# openSX70_PATHFINDER_V5_6-SEEED_20180611.net
KiCad netlist of a schematic drawn in EAGLE
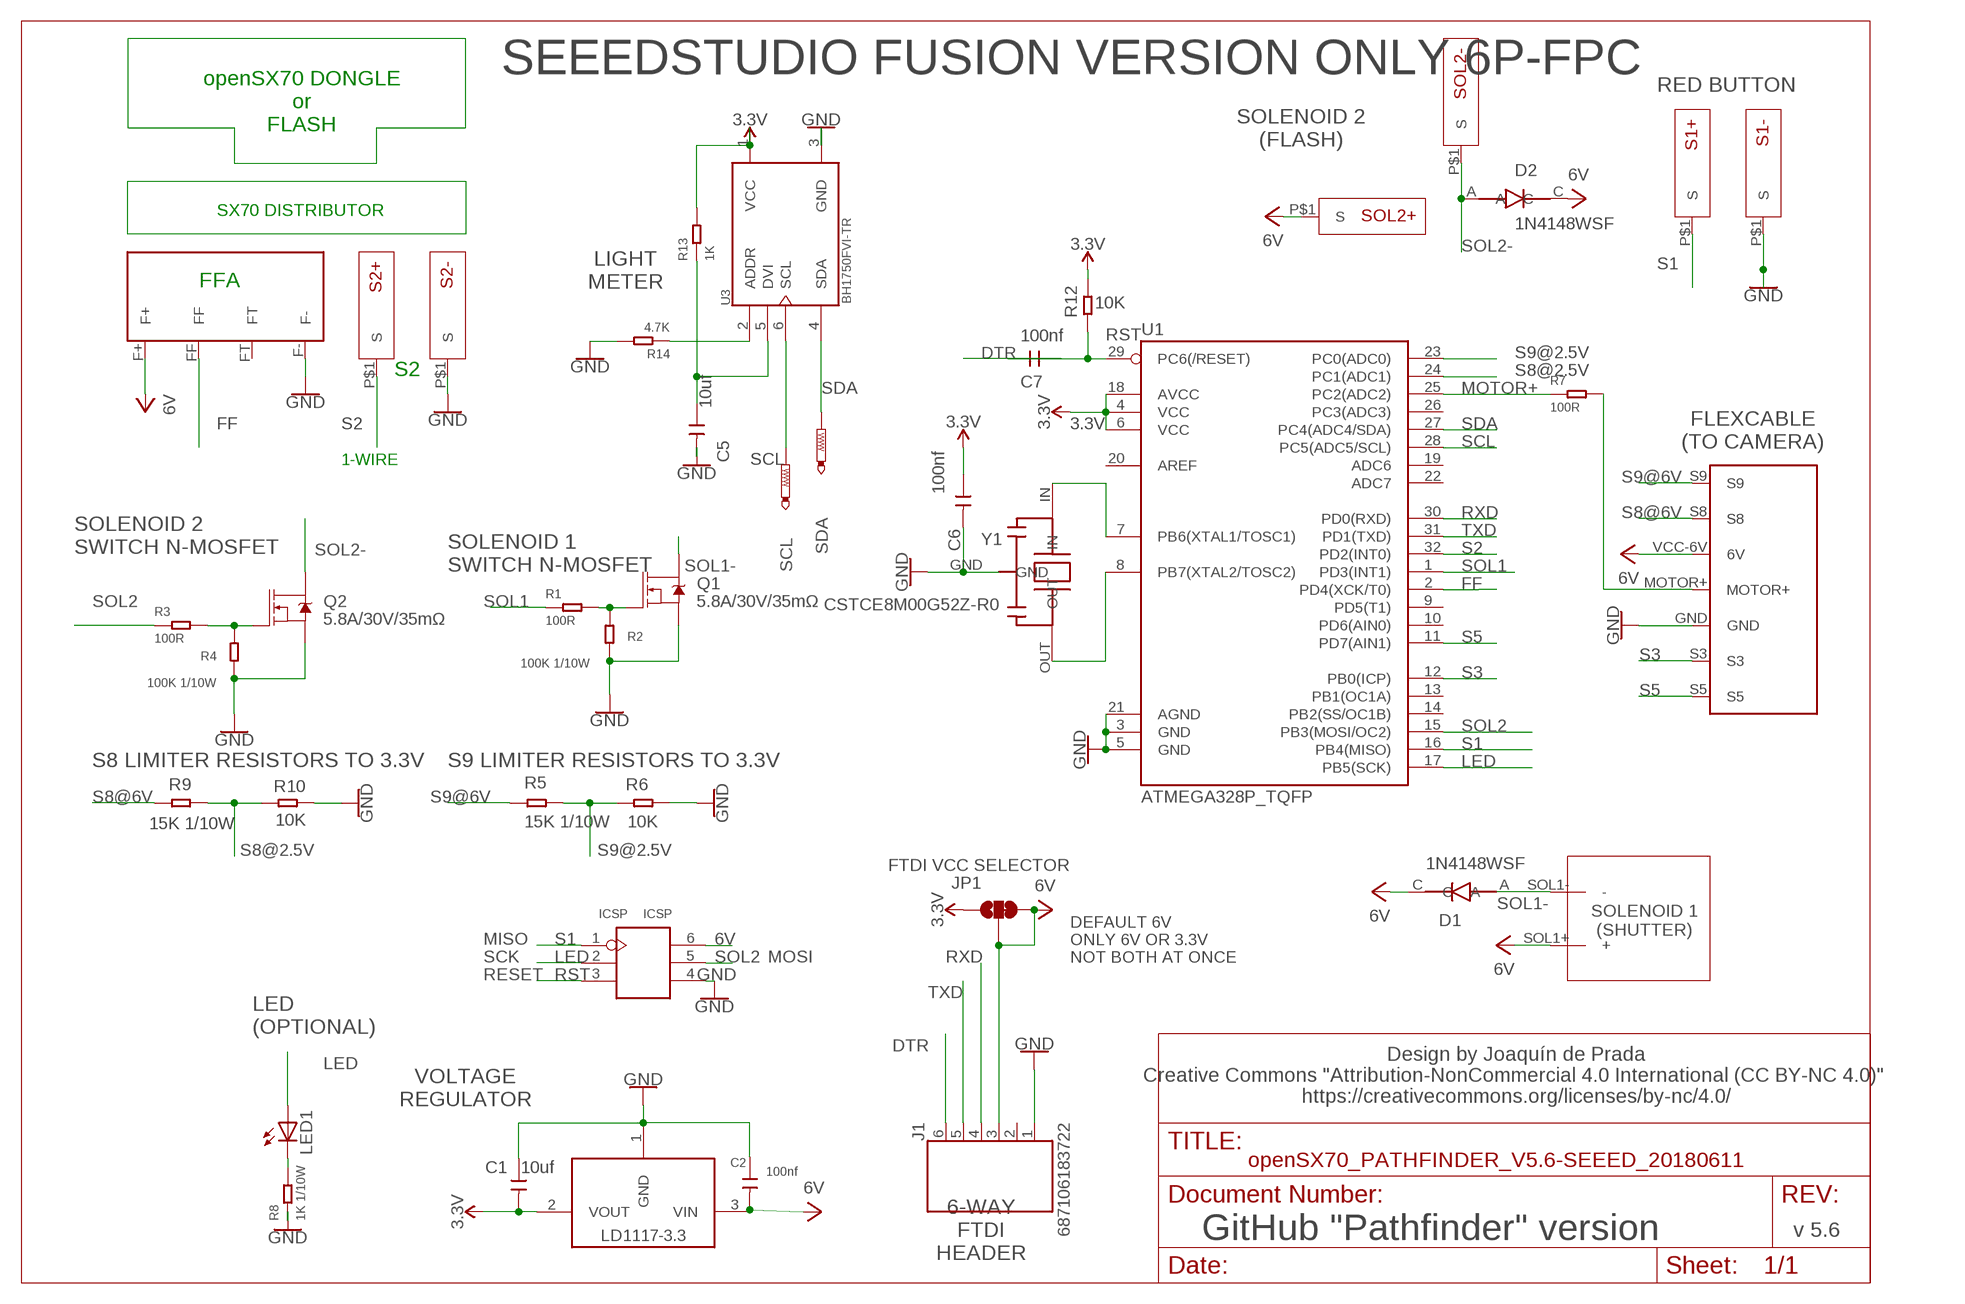
[diagram p0: schematic, sheet 1]

(export (version "E")
  (design (tool "Eeschema 10.0.6"))
  (components
    (comp (ref "C1")
      (value "10uf")
      (footprint "eagle-import:C0603")
      (fields (field (name "MPN") "CC0603KRX5R6BB106"))
      (libsource (lib "eagle-import") (part "CERAMIC-10UF-10V-10%-X5R(0603)"))
    )
    (comp (ref "C2")
      (value "100nf")
      (footprint "eagle-import:C0603")
      (fields (field (name "MPN") "CC0603KRX7R9BB104"))
      (libsource (lib "eagle-import") (part "CERAMIC-100NF-50V-10%-X7R(0603)"))
    )
    (comp (ref "C5")
      (value "10uf")
      (footprint "eagle-import:C0603")
      (fields (field (name "MPN") "CC0603KRX5R6BB106"))
      (libsource (lib "eagle-import") (part "CERAMIC-10UF-10V-10%-X5R(0603)"))
    )
    (comp (ref "C6")
      (value "100nf")
      (footprint "eagle-import:C0603")
      (fields (field (name "MPN") "CC0603KRX7R9BB104"))
      (libsource (lib "eagle-import") (part "CERAMIC-100NF-50V-10%-X7R(0603)"))
    )
    (comp (ref "C7")
      (value "100nf")
      (footprint "eagle-import:C0603")
      (fields (field (name "MPN") "CC0603KRX7R9BB104"))
      (libsource (lib "eagle-import") (part "CERAMIC-100NF-50V-10%-X7R(0603)"))
    )
    (comp (ref "D1")
      (value "1N4148WSF")
      (footprint "eagle-import:SODFL2512X100N")
      (fields (field (name "MANUFACTURER") "Fairchild Semiconductor"))
      (libsource (lib "eagle-import") (part "1N4148WS"))
    )
    (comp (ref "D2")
      (value "1N4148WSF")
      (footprint "eagle-import:SODFL2512X100N")
      (fields (field (name "MANUFACTURER") "Fairchild Semiconductor"))
      (libsource (lib "eagle-import") (part "1N4148WS"))
    )
    (comp (ref "ICSP")
      (value "ICSP")
      (footprint "eagle-import:H2X3-2.54")
      (libsource (lib "eagle-import") (part "ICSP"))
    )
    (comp (ref "J1")
      (value "687106183722")
      (footprint "eagle-import:687106183722")
      (fields (field (name "MF") "Wurth Electronics"))
      (libsource (lib "eagle-import") (part "687106183722"))
    )
    (comp (ref "JP1")
      (value "FTDI VCC SELECTOR")
      (footprint "eagle-import:SMT-JUMPER_3_1-NC_TRACE_SILK")
      (libsource (lib "eagle-import") (part "JUMPER-SMT_3_1-NC_TRACE_SILK"))
    )
    (comp (ref "LD11172.5V")
      (value "LD1117 2.5V")
      (footprint "eagle-import:SOT223")
      (fields (field (name "MF") "Advanced Monolithic Systems") (field (name "MP") "AMS1117-5.0"))
      (libsource (lib "eagle-import") (part "LD1117-3.3"))
    )
    (comp (ref "LED1")
      (value "LEDCHIPLED_0805")
      (footprint "eagle-import:CHIPLED_0805")
      (libsource (lib "eagle-import") (part "LEDCHIPLED_0805"))
    )
    (comp (ref "Q1")
      (value "5.8A/30V/35mΩ")
      (footprint "eagle-import:SOT23-3")
      (libsource (lib "eagle-import") (part "MOSFET-NCH-AO3404A"))
    )
    (comp (ref "Q2")
      (value "5.8A/30V/35mΩ")
      (footprint "eagle-import:SOT23-3")
      (libsource (lib "eagle-import") (part "MOSFET-NCH-AO3404A"))
    )
    (comp (ref "R1")
      (value "100R")
      (footprint "eagle-import:R0603")
      (fields (field (name "MPN") "RC0603JR-07100RL"))
      (libsource (lib "eagle-import") (part "SMD-RES-100R-5%-1/10W(0603)"))
    )
    (comp (ref "R2")
      (value "100K 1/10W")
      (footprint "eagle-import:R0603")
      (fields (field (name "MPN") "RC0603JR-07100KL"))
      (libsource (lib "eagle-import") (part "SMD-RES-100K-5%-1/10W(0603)"))
    )
    (comp (ref "R3")
      (value "100R")
      (footprint "eagle-import:R0603")
      (fields (field (name "MPN") "RC0603JR-07100RL"))
      (libsource (lib "eagle-import") (part "SMD-RES-100R-5%-1/10W(0603)"))
    )
    (comp (ref "R4")
      (value "100K 1/10W")
      (footprint "eagle-import:R0603")
      (fields (field (name "MPN") "RC0603JR-07100KL"))
      (libsource (lib "eagle-import") (part "SMD-RES-100K-5%-1/10W(0603)"))
    )
    (comp (ref "R5")
      (value "15K 1/10W")
      (footprint "eagle-import:R0603")
      (fields (field (name "MPN") "RC0603FR-0715KL"))
      (libsource (lib "eagle-import") (part "SMD-RES-15K-1%-1/10W(0603)"))
    )
    (comp (ref "R6")
      (value "10K")
      (footprint "eagle-import:R0603")
      (fields (field (name "MPN") "RC0603FR-0710KL"))
      (libsource (lib "eagle-import") (part "SMD-RES-10K-1%-1/10W(0603)"))
    )
    (comp (ref "R7")
      (value "100R")
      (footprint "eagle-import:R0603")
      (fields (field (name "MPN") "RC0603JR-07100RL"))
      (libsource (lib "eagle-import") (part "SMD-RES-100R-5%-1/10W(0603)"))
    )
    (comp (ref "R8")
      (value "1K 1/10W")
      (footprint "eagle-import:R0603")
      (fields (field (name "MPN") "RC0603JR-071KL"))
      (libsource (lib "eagle-import") (part "SMD-RES-1K-5%-1/10W(0603)"))
    )
    (comp (ref "R9")
      (value "15K 1/10W")
      (footprint "eagle-import:R0603")
      (fields (field (name "MPN") "RC0603FR-0715KL"))
      (libsource (lib "eagle-import") (part "SMD-RES-15K-1%-1/10W(0603)"))
    )
    (comp (ref "R10")
      (value "10K")
      (footprint "eagle-import:R0603")
      (fields (field (name "MPN") "RC0603FR-0710KL"))
      (libsource (lib "eagle-import") (part "SMD-RES-10K-1%-1/10W(0603)"))
    )
    (comp (ref "R12")
      (value "10K")
      (footprint "eagle-import:R0603")
      (fields (field (name "MPN") "RC0603FR-0710KL"))
      (libsource (lib "eagle-import") (part "SMD-RES-10K-1%-1/10W(0603)"))
    )
    (comp (ref "R13")
      (value "1K")
      (footprint "eagle-import:R0603")
      (fields (field (name "MPN") "RC0603FR-071KL"))
      (libsource (lib "eagle-import") (part "SMD-RES-1K-1%-1/10W(0603)"))
    )
    (comp (ref "R14")
      (value "4.7K")
      (footprint "eagle-import:R0603")
      (fields (field (name "MPN") "RC0603JR-074K7L"))
      (libsource (lib "eagle-import") (part "SMD-RES-4.7K-5%-1/10W(0603)"))
    )
    (comp (ref "S1+")
      (value "SX70-S-PAD-NEW")
      (footprint "eagle-import:SX70-S-PAD2")
      (libsource (lib "eagle-import") (part "SX70-S-PAD-NEW"))
    )
    (comp (ref "S1-")
      (value "SX70-S-PAD-NEW")
      (footprint "eagle-import:SX70-S-PAD2")
      (libsource (lib "eagle-import") (part "SX70-S-PAD-NEW"))
    )
    (comp (ref "S2+")
      (value "SX70-S-PAD-NEW")
      (footprint "eagle-import:SX70-S-PAD2")
      (libsource (lib "eagle-import") (part "SX70-S-PAD-NEW"))
    )
    (comp (ref "S2-")
      (value "SX70-S-PAD-NEW")
      (footprint "eagle-import:SX70-S-PAD2")
      (libsource (lib "eagle-import") (part "SX70-S-PAD-NEW"))
    )
    (comp (ref "SCL")
      (value "PTR1TP08R")
      (footprint "eagle-import:TP08R")
      (libsource (lib "eagle-import") (part "PTR1TP08R"))
    )
    (comp (ref "SDA")
      (value "PTR1TP08R")
      (footprint "eagle-import:TP08R")
      (libsource (lib "eagle-import") (part "PTR1TP08R"))
    )
    (comp (ref "SOL1")
      (value "SX70-SOLENOID1-2PADS")
      (footprint "eagle-import:SX70-SOLENOID1-2")
      (libsource (lib "eagle-import") (part "SX70-SOLENOID1-2PADS"))
    )
    (comp (ref "SOL2+")
      (value "SX70-S-PAD-NEW")
      (footprint "eagle-import:SX70-S-PAD2")
      (libsource (lib "eagle-import") (part "SX70-S-PAD-NEW"))
    )
    (comp (ref "SOL2-")
      (value "SX70-S-PAD-NEW")
      (footprint "eagle-import:SX70-S-PAD2")
      (libsource (lib "eagle-import") (part "SX70-S-PAD-NEW"))
    )
    (comp (ref "U$1")
      (value "SX70-7-PAD")
      (footprint "eagle-import:SX70-7-PAD")
      (libsource (lib "eagle-import") (part "SX70-7-PAD"))
    )
    (comp (ref "U$2")
      (value "FFA")
      (footprint "eagle-import:FFA-PAD-PACKAGE")
      (libsource (lib "eagle-import") (part "SX70-FFA-PAD"))
    )
    (comp (ref "U1")
      (value "ATMEGA328P_TQFP")
      (footprint "eagle-import:TQFP32-08")
      (libsource (lib "eagle-import") (part "ATMEGA328P_TQFP"))
    )
    (comp (ref "U3")
      (value "BH1750FVI-TR")
      (footprint "eagle-import:SOTFL50P300X75-6N")
      (fields (field (name "MF") "Rohm"))
      (libsource (lib "eagle-import") (part "BH1750FVI-TR"))
    )
    (comp (ref "Y1")
      (value "CSTCE8M00G52Z-R0")
      (footprint "eagle-import:CFP95P160X100-3N")
      (fields (field (name "MF") "Murata") (field (name "MP") "CSTCE16M0V53-R0"))
      (libsource (lib "eagle-import") (part "CSTCE16M0V53-R0"))
    )
  )
  (nets
    (net (code "1") (name "/DTR") (class "Default")
      (node (ref "C7") (pin "1") (pinfunction "1_1") (pintype "passive"))
      (node (ref "J1") (pin "6") (pinfunction "1_6") (pintype "passive"))
    )
    (net (code "2") (name "/FF") (class "Default")
      (node (ref "U$2") (pin "FF") (pinfunction "FF_FF") (pintype "bidirectional"))
      (node (ref "U1") (pin "2") (pinfunction "PD4(XCK/T0)_2") (pintype "bidirectional"))
    )
    (net (code "3") (name "/LED") (class "Default")
      (node (ref "ICSP") (pin "2") (pinfunction "SCK_2") (pintype "bidirectional"))
      (node (ref "LED1") (pin "A") (pinfunction "A_A") (pintype "passive"))
      (node (ref "U1") (pin "17") (pinfunction "PB5(SCK)_17") (pintype "bidirectional"))
    )
    (net (code "4") (name "/MOTOR+") (class "Default")
      (node (ref "R7") (pin "1") (pinfunction "1_1") (pintype "passive"))
      (node (ref "U1") (pin "25") (pinfunction "PC2(ADC2)_25") (pintype "bidirectional"))
    )
    (net (code "5") (name "/RST") (class "Default")
      (node (ref "C7") (pin "2") (pinfunction "2_2") (pintype "passive"))
      (node (ref "ICSP") (pin "3") (pinfunction "RST_3") (pintype "bidirectional"))
      (node (ref "R12") (pin "1") (pinfunction "1_1") (pintype "passive"))
      (node (ref "U1") (pin "29") (pinfunction "PC6(/RESET)_29") (pintype "bidirectional"))
    )
    (net (code "6") (name "/RXD") (class "Default")
      (node (ref "J1") (pin "4") (pinfunction "3_4") (pintype "passive"))
      (node (ref "U1") (pin "30") (pinfunction "PD0(RXD)_30") (pintype "bidirectional"))
    )
    (net (code "7") (name "/S1") (class "Default")
      (node (ref "ICSP") (pin "1") (pinfunction "MISO_1") (pintype "bidirectional"))
      (node (ref "S1+") (pin "P$1") (pinfunction "S_P$1") (pintype "bidirectional"))
      (node (ref "U1") (pin "16") (pinfunction "PB4(MISO)_16") (pintype "bidirectional"))
    )
    (net (code "8") (name "/S2") (class "Default")
      (node (ref "S2+") (pin "P$1") (pinfunction "S_P$1") (pintype "bidirectional"))
      (node (ref "U1") (pin "32") (pinfunction "PD2(INT0)_32") (pintype "bidirectional"))
    )
    (net (code "9") (name "/S3") (class "Default")
      (node (ref "U$1") (pin "S3") (pinfunction "S3_S3") (pintype "bidirectional"))
      (node (ref "U1") (pin "12") (pinfunction "PB0(ICP)_12") (pintype "bidirectional"))
    )
    (net (code "10") (name "/S5") (class "Default")
      (node (ref "U$1") (pin "S5") (pinfunction "S5_S5") (pintype "bidirectional"))
      (node (ref "U1") (pin "11") (pinfunction "PD7(AIN1)_11") (pintype "bidirectional"))
    )
    (net (code "11") (name "/S8@2.5V") (class "Default")
      (node (ref "R10") (pin "1") (pinfunction "1_1") (pintype "passive"))
      (node (ref "R9") (pin "2") (pinfunction "2_2") (pintype "passive"))
      (node (ref "U1") (pin "24") (pinfunction "PC1(ADC1)_24") (pintype "bidirectional"))
    )
    (net (code "12") (name "/S8@6V") (class "Default")
      (node (ref "R9") (pin "1") (pinfunction "1_1") (pintype "passive"))
      (node (ref "U$1") (pin "S8") (pinfunction "S8_S8") (pintype "bidirectional"))
    )
    (net (code "13") (name "/S9@2.5V") (class "Default")
      (node (ref "R5") (pin "2") (pinfunction "2_2") (pintype "passive"))
      (node (ref "R6") (pin "1") (pinfunction "1_1") (pintype "passive"))
      (node (ref "U1") (pin "23") (pinfunction "PC0(ADC0)_23") (pintype "bidirectional"))
    )
    (net (code "14") (name "/S9@6V") (class "Default")
      (node (ref "R5") (pin "1") (pinfunction "1_1") (pintype "passive"))
      (node (ref "U$1") (pin "S9") (pinfunction "S9_S9") (pintype "bidirectional"))
    )
    (net (code "15") (name "/SCL") (class "Default")
      (node (ref "SCL") (pin "TP") (pinfunction "TP_TP") (pintype "input"))
      (node (ref "U1") (pin "28") (pinfunction "PC5(ADC5/SCL)_28") (pintype "bidirectional"))
      (node (ref "U3") (pin "6") (pinfunction "SCL_6") (pintype "input"))
    )
    (net (code "16") (name "/SDA") (class "Default")
      (node (ref "SDA") (pin "TP") (pinfunction "TP_TP") (pintype "input"))
      (node (ref "U1") (pin "27") (pinfunction "PC4(ADC4/SDA)_27") (pintype "bidirectional"))
      (node (ref "U3") (pin "4") (pinfunction "SDA_4") (pintype "bidirectional"))
    )
    (net (code "17") (name "/SOL1") (class "Default")
      (node (ref "R1") (pin "1") (pinfunction "1_1") (pintype "passive"))
      (node (ref "U1") (pin "1") (pinfunction "PD3(INT1)_1") (pintype "bidirectional"))
    )
    (net (code "18") (name "/SOL1-") (class "Default")
      (node (ref "D1") (pin "A") (pinfunction "A_A") (pintype "passive"))
      (node (ref "Q1") (pin "3") (pinfunction "D_3") (pintype "bidirectional"))
      (node (ref "SOL1") (pin "SOL1-") (pinfunction "-_SOL1-") (pintype "bidirectional"))
    )
    (net (code "19") (name "/SOL2") (class "Default")
      (node (ref "ICSP") (pin "5") (pinfunction "MOSI_5") (pintype "bidirectional"))
      (node (ref "R3") (pin "1") (pinfunction "1_1") (pintype "passive"))
      (node (ref "U1") (pin "15") (pinfunction "PB3(MOSI/OC2)_15") (pintype "bidirectional"))
    )
    (net (code "20") (name "/SOL2-") (class "Default")
      (node (ref "D2") (pin "A") (pinfunction "A_A") (pintype "passive"))
      (node (ref "Q2") (pin "3") (pinfunction "D_3") (pintype "bidirectional"))
      (node (ref "SOL2-") (pin "P$1") (pinfunction "S_P$1") (pintype "bidirectional"))
    )
    (net (code "21") (name "/TXD") (class "Default")
      (node (ref "J1") (pin "5") (pinfunction "2_5") (pintype "passive"))
      (node (ref "U1") (pin "31") (pinfunction "PD1(TXD)_31") (pintype "bidirectional"))
    )
    (net (code "22") (name "3.3V") (class "Default")
      (node (ref "C1") (pin "2") (pinfunction "2_2") (pintype "passive"))
      (node (ref "C6") (pin "1") (pinfunction "1_1") (pintype "passive"))
      (node (ref "JP1") (pin "1") (pinfunction "1_1") (pintype "passive"))
      (node (ref "LD11172.5V") (pin "2") (pinfunction "VOUT_2") (pintype "bidirectional"))
      (node (ref "R12") (pin "2") (pinfunction "2_2") (pintype "passive"))
      (node (ref "R13") (pin "2") (pinfunction "2_2") (pintype "passive"))
      (node (ref "U1") (pin "18") (pinfunction "AVCC_18") (pintype "bidirectional"))
      (node (ref "U1") (pin "4") (pinfunction "VCC_4") (pintype "bidirectional"))
      (node (ref "U1") (pin "6") (pinfunction "VCC_6") (pintype "bidirectional"))
      (node (ref "U3") (pin "1") (pinfunction "VCC_1") (pintype "power_in"))
    )
    (net (code "23") (name "6V") (class "Default")
      (node (ref "C2") (pin "2") (pinfunction "2_2") (pintype "passive"))
      (node (ref "D1") (pin "C") (pinfunction "C_C") (pintype "passive"))
      (node (ref "D2") (pin "C") (pinfunction "C_C") (pintype "passive"))
      (node (ref "ICSP") (pin "6") (pinfunction "VCC_6") (pintype "bidirectional"))
      (node (ref "J1") (pin "3") (pinfunction "4_3") (pintype "passive"))
      (node (ref "JP1") (pin "2") (pinfunction "2_2") (pintype "passive"))
      (node (ref "JP1") (pin "3") (pinfunction "3_3") (pintype "passive"))
      (node (ref "LD11172.5V") (pin "3") (pinfunction "VIN_3") (pintype "bidirectional"))
      (node (ref "SOL1") (pin "SOL1+") (pinfunction "+_SOL1+") (pintype "bidirectional"))
      (node (ref "SOL2+") (pin "P$1") (pinfunction "S_P$1") (pintype "bidirectional"))
      (node (ref "U$1") (pin "VCC-6V") (pinfunction "6V_VCC-6V") (pintype "bidirectional"))
      (node (ref "U$2") (pin "F+") (pinfunction "F+_F+") (pintype "bidirectional"))
    )
    (net (code "24") (name "GND") (class "Default")
      (node (ref "C1") (pin "1") (pinfunction "1_1") (pintype "passive"))
      (node (ref "C2") (pin "1") (pinfunction "1_1") (pintype "passive"))
      (node (ref "C5") (pin "2") (pinfunction "2_2") (pintype "passive"))
      (node (ref "C6") (pin "2") (pinfunction "2_2") (pintype "passive"))
      (node (ref "ICSP") (pin "4") (pinfunction "GND_4") (pintype "bidirectional"))
      (node (ref "J1") (pin "1") (pinfunction "6_1") (pintype "passive"))
      (node (ref "LD11172.5V") (pin "1") (pinfunction "GND_1") (pintype "bidirectional"))
      (node (ref "Q1") (pin "2") (pinfunction "S_2") (pintype "bidirectional"))
      (node (ref "Q2") (pin "2") (pinfunction "S_2") (pintype "bidirectional"))
      (node (ref "R10") (pin "2") (pinfunction "2_2") (pintype "passive"))
      (node (ref "R14") (pin "2") (pinfunction "2_2") (pintype "passive"))
      (node (ref "R2") (pin "1") (pinfunction "1_1") (pintype "passive"))
      (node (ref "R4") (pin "1") (pinfunction "1_1") (pintype "passive"))
      (node (ref "R6") (pin "2") (pinfunction "2_2") (pintype "passive"))
      (node (ref "R8") (pin "1") (pinfunction "1_1") (pintype "passive"))
      (node (ref "S1-") (pin "P$1") (pinfunction "S_P$1") (pintype "bidirectional"))
      (node (ref "S2-") (pin "P$1") (pinfunction "S_P$1") (pintype "bidirectional"))
      (node (ref "U$1") (pin "GND") (pinfunction "GND_GND") (pintype "bidirectional"))
      (node (ref "U$2") (pin "F-") (pinfunction "F-_F-") (pintype "bidirectional"))
      (node (ref "U1") (pin "21") (pinfunction "AGND_21") (pintype "bidirectional"))
      (node (ref "U1") (pin "3") (pinfunction "GND_3") (pintype "bidirectional"))
      (node (ref "U1") (pin "5") (pinfunction "GND_5") (pintype "bidirectional"))
      (node (ref "U3") (pin "3") (pinfunction "GND_3") (pintype "power_in"))
      (node (ref "Y1") (pin "GND") (pinfunction "GND_GND") (pintype "passive"))
    )
    (net (code "25") (name "Net-(LED1-PadC)") (class "Default")
      (node (ref "LED1") (pin "C") (pinfunction "C_C") (pintype "passive"))
      (node (ref "R8") (pin "2") (pinfunction "2_2") (pintype "passive"))
    )
    (net (code "26") (name "Net-(Q1-G)") (class "Default")
      (node (ref "Q1") (pin "1") (pinfunction "G_1") (pintype "bidirectional"))
      (node (ref "R1") (pin "2") (pinfunction "2_2") (pintype "passive"))
      (node (ref "R2") (pin "2") (pinfunction "2_2") (pintype "passive"))
    )
    (net (code "27") (name "Net-(Q2-G)") (class "Default")
      (node (ref "Q2") (pin "1") (pinfunction "G_1") (pintype "bidirectional"))
      (node (ref "R3") (pin "2") (pinfunction "2_2") (pintype "passive"))
      (node (ref "R4") (pin "2") (pinfunction "2_2") (pintype "passive"))
    )
    (net (code "28") (name "Net-(R7-Pad2)") (class "Default")
      (node (ref "R7") (pin "2") (pinfunction "2_2") (pintype "passive"))
      (node (ref "U$1") (pin "MOTOR+") (pinfunction "MOTOR+_MOTOR+") (pintype "bidirectional"))
    )
    (net (code "29") (name "Net-(U1-PB6(XTAL1{slash}TOSC1))") (class "Default")
      (node (ref "U1") (pin "7") (pinfunction "PB6(XTAL1/TOSC1)_7") (pintype "bidirectional"))
      (node (ref "Y1") (pin "IN") (pinfunction "IN_IN") (pintype "input"))
    )
    (net (code "30") (name "Net-(U1-PB7(XTAL2{slash}TOSC2))") (class "Default")
      (node (ref "U1") (pin "8") (pinfunction "PB7(XTAL2/TOSC2)_8") (pintype "bidirectional"))
      (node (ref "Y1") (pin "OUT") (pinfunction "OUT_OUT") (pintype "output"))
    )
    (net (code "31") (name "Net-(U3-ADDR)") (class "Default")
      (node (ref "R14") (pin "1") (pinfunction "1_1") (pintype "passive"))
      (node (ref "U3") (pin "2") (pinfunction "ADDR_2") (pintype "input"))
    )
    (net (code "32") (name "Net-(U3-DVI)") (class "Default")
      (node (ref "C5") (pin "1") (pinfunction "1_1") (pintype "passive"))
      (node (ref "R13") (pin "1") (pinfunction "1_1") (pintype "passive"))
      (node (ref "U3") (pin "5") (pinfunction "DVI_5") (pintype "input"))
    )
    (net (code "33") (name "unconnected-(J1-5-Pad2)") (class "Default")
      (node (ref "J1") (pin "2") (pinfunction "5_2") (pintype "passive"))
    )
    (net (code "34") (name "unconnected-(U$2-PadFT)") (class "Default")
      (node (ref "U$2") (pin "FT") (pinfunction "FT_FT") (pintype "bidirectional"))
    )
    (net (code "35") (name "unconnected-(U1-ADC6-Pad19)") (class "Default")
      (node (ref "U1") (pin "19") (pinfunction "ADC6_19") (pintype "bidirectional"))
    )
    (net (code "36") (name "unconnected-(U1-ADC7-Pad22)") (class "Default")
      (node (ref "U1") (pin "22") (pinfunction "ADC7_22") (pintype "bidirectional"))
    )
    (net (code "37") (name "unconnected-(U1-AREF-Pad20)") (class "Default")
      (node (ref "U1") (pin "20") (pinfunction "AREF_20") (pintype "bidirectional"))
    )
    (net (code "38") (name "unconnected-(U1-PB1(OC1A)-Pad13)") (class "Default")
      (node (ref "U1") (pin "13") (pinfunction "PB1(OC1A)_13") (pintype "bidirectional"))
    )
    (net (code "39") (name "unconnected-(U1-PB2(SS{slash}OC1B)-Pad14)") (class "Default")
      (node (ref "U1") (pin "14") (pinfunction "PB2(SS/OC1B)_14") (pintype "bidirectional"))
    )
    (net (code "40") (name "unconnected-(U1-PC3(ADC3)-Pad26)") (class "Default")
      (node (ref "U1") (pin "26") (pinfunction "PC3(ADC3)_26") (pintype "bidirectional"))
    )
    (net (code "41") (name "unconnected-(U1-PD5(T1)-Pad9)") (class "Default")
      (node (ref "U1") (pin "9") (pinfunction "PD5(T1)_9") (pintype "bidirectional"))
    )
    (net (code "42") (name "unconnected-(U1-PD6(AIN0)-Pad10)") (class "Default")
      (node (ref "U1") (pin "10") (pinfunction "PD6(AIN0)_10") (pintype "bidirectional"))
    )
  )
)
